# incubatorShield.net
KiCad netlist of a schematic drawn in EAGLE
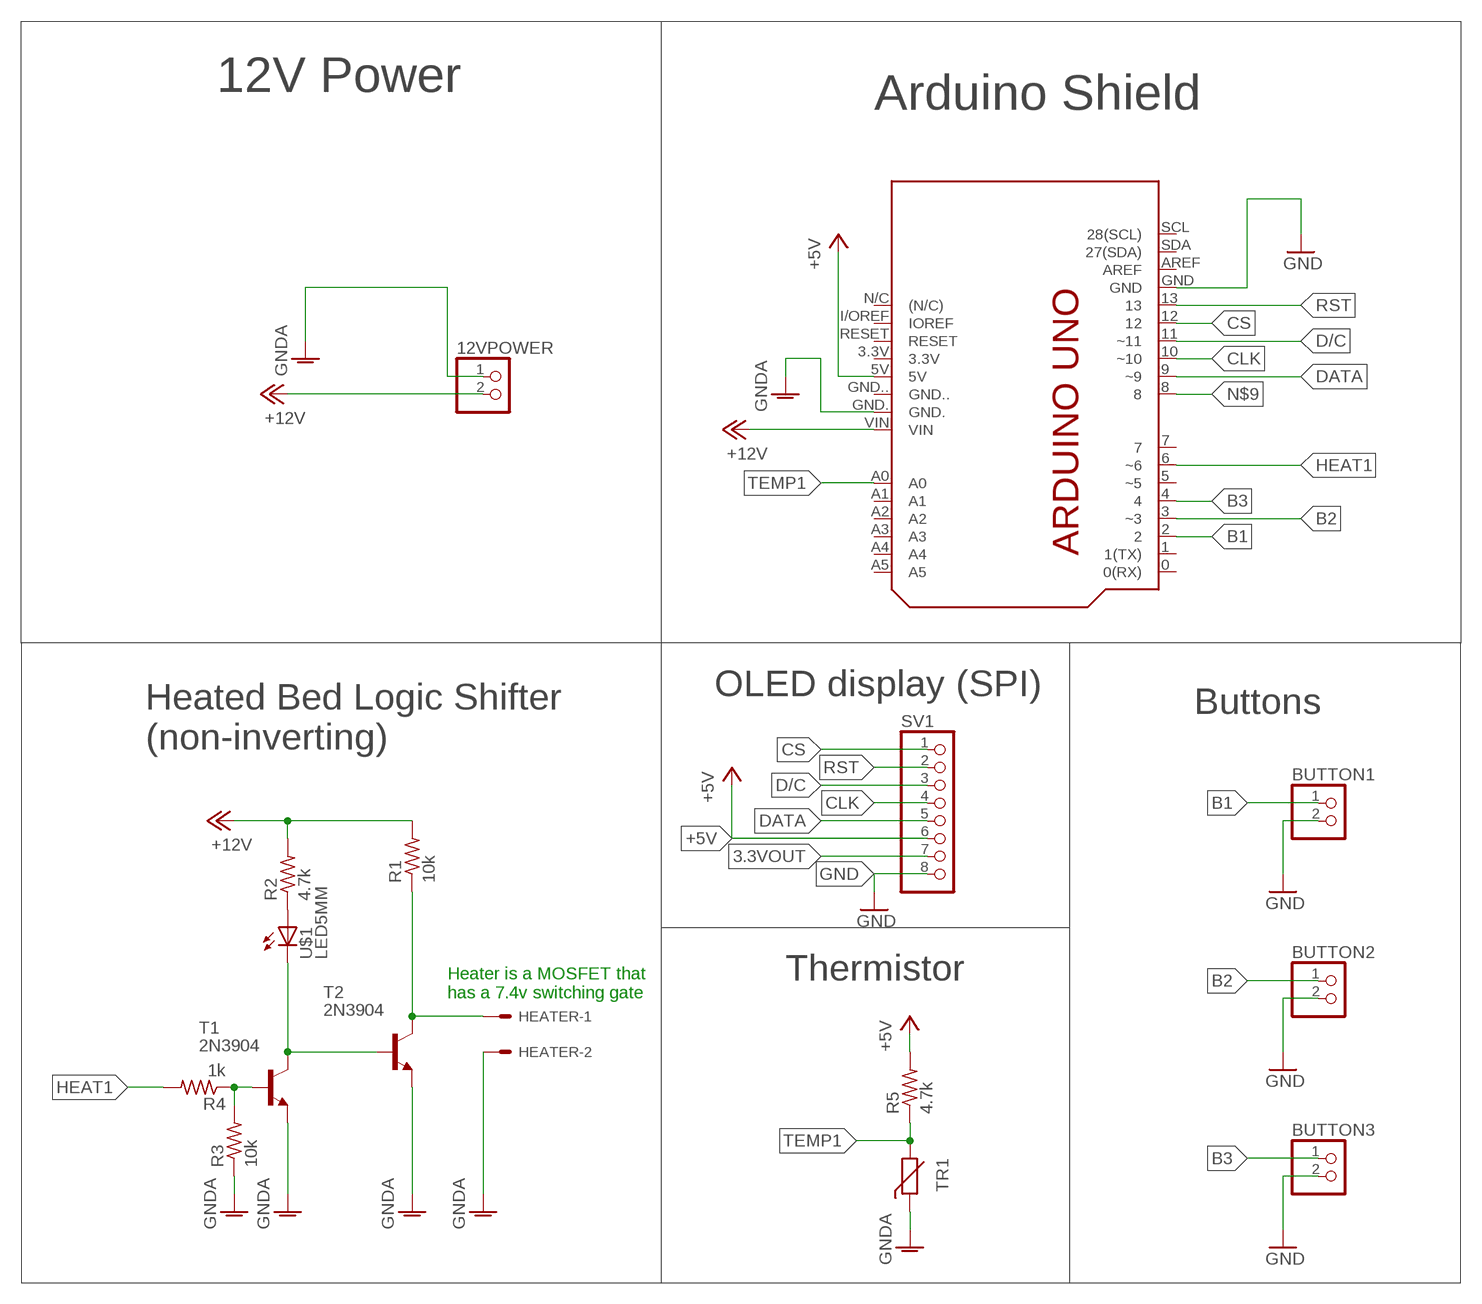
[diagram p0: schematic, sheet 1]

(export (version "E")
  (design (tool "Eeschema 10.0.6"))
  (components
    (comp (ref "12VPOWER")
      (value "PINHD-1X2")
      (footprint "eagle-import:1X02")
      (libsource (lib "eagle-import") (part "PINHD-1X2"))
    )
    (comp (ref "BUTTON1")
      (value "PINHD-1X2")
      (footprint "eagle-import:1X02")
      (libsource (lib "eagle-import") (part "PINHD-1X2"))
    )
    (comp (ref "BUTTON2")
      (value "PINHD-1X2")
      (footprint "eagle-import:1X02")
      (libsource (lib "eagle-import") (part "PINHD-1X2"))
    )
    (comp (ref "BUTTON3")
      (value "PINHD-1X2")
      (footprint "eagle-import:1X02")
      (libsource (lib "eagle-import") (part "PINHD-1X2"))
    )
    (comp (ref "HEATER")
      (value "KK-156-2")
      (footprint "eagle-import:KK-156-2")
      (fields (field (name "MF") "MOLEX"))
      (libsource (lib "eagle-import") (part "KK-156-2"))
    )
    (comp (ref "R1")
      (value "10k")
      (footprint "eagle-import:0309_12")
      (libsource (lib "eagle-import") (part "R-US_0309/12"))
    )
    (comp (ref "R2")
      (value "4.7k")
      (footprint "eagle-import:0309_12")
      (libsource (lib "eagle-import") (part "R-US_0309/12"))
    )
    (comp (ref "R3")
      (value "10k")
      (footprint "eagle-import:0309_12")
      (libsource (lib "eagle-import") (part "R-US_0309/12"))
    )
    (comp (ref "R4")
      (value "1k")
      (footprint "eagle-import:0309_12")
      (libsource (lib "eagle-import") (part "R-US_0309/12"))
    )
    (comp (ref "R5")
      (value "4.7k")
      (footprint "eagle-import:0309_12")
      (libsource (lib "eagle-import") (part "R-US_0309/12"))
    )
    (comp (ref "SV1")
      (value "PINHD-1X8")
      (footprint "eagle-import:1X08")
      (libsource (lib "eagle-import") (part "PINHD-1X8"))
    )
    (comp (ref "T1")
      (value "2N3904")
      (footprint "eagle-import:TO92")
      (libsource (lib "eagle-import") (part "2N3904"))
    )
    (comp (ref "T2")
      (value "2N3904")
      (footprint "eagle-import:TO92")
      (libsource (lib "eagle-import") (part "2N3904"))
    )
    (comp (ref "TR1")
      (value "THERMISTOR_R-2,5")
      (footprint "eagle-import:RS-2,5")
      (libsource (lib "eagle-import") (part "THERMISTOR_R-2,5"))
    )
    (comp (ref "U$1")
      (value "LED5MM")
      (footprint "eagle-import:5MM")
      (libsource (lib "eagle-import") (part "LED5MM"))
    )
    (comp (ref "U$2")
      (value "ARDUINO_UNO_UNBOUND")
      (footprint "eagle-import:ARDUINO_UNO_UNBOUND")
      (libsource (lib "eagle-import") (part "ARDUINO_UNO_UNBOUND"))
    )
  )
  (nets
    (net (code "1") (name "+5V") (class "Default")
      (node (ref "R5") (pin "2") (pinfunction "2_2") (pintype "passive"))
      (node (ref "SV1") (pin "6") (pinfunction "6_6") (pintype "passive"))
      (node (ref "U$2") (pin "5V") (pinfunction "5V_5V") (pintype "bidirectional"))
    )
    (net (code "2") (name "+12V") (class "Default")
      (node (ref "12VPOWER") (pin "2") (pinfunction "2_2") (pintype "passive"))
      (node (ref "R1") (pin "2") (pinfunction "2_2") (pintype "passive"))
      (node (ref "R2") (pin "2") (pinfunction "2_2") (pintype "passive"))
      (node (ref "U$2") (pin "VIN") (pinfunction "VIN_VIN") (pintype "bidirectional"))
    )
    (net (code "3") (name "3.3VOUT") (class "Default")
      (node (ref "SV1") (pin "7") (pinfunction "7_7") (pintype "passive"))
    )
    (net (code "4") (name "B1") (class "Default")
      (node (ref "BUTTON1") (pin "1") (pinfunction "1_1") (pintype "passive"))
      (node (ref "U$2") (pin "2") (pinfunction "2_2") (pintype "bidirectional"))
    )
    (net (code "5") (name "B2") (class "Default")
      (node (ref "BUTTON2") (pin "1") (pinfunction "1_1") (pintype "passive"))
      (node (ref "U$2") (pin "3") (pinfunction "~{3}_3") (pintype "bidirectional"))
    )
    (net (code "6") (name "B3") (class "Default")
      (node (ref "BUTTON3") (pin "1") (pinfunction "1_1") (pintype "passive"))
      (node (ref "U$2") (pin "4") (pinfunction "4_4") (pintype "bidirectional"))
    )
    (net (code "7") (name "CLK") (class "Default")
      (node (ref "SV1") (pin "4") (pinfunction "4_4") (pintype "passive"))
      (node (ref "U$2") (pin "10") (pinfunction "~{10}_10") (pintype "bidirectional"))
    )
    (net (code "8") (name "CS") (class "Default")
      (node (ref "SV1") (pin "1") (pinfunction "1_1") (pintype "passive"))
      (node (ref "U$2") (pin "12") (pinfunction "12_12") (pintype "bidirectional"))
    )
    (net (code "9") (name "DATA") (class "Default")
      (node (ref "SV1") (pin "5") (pinfunction "5_5") (pintype "passive"))
      (node (ref "U$2") (pin "9") (pinfunction "~{9}_9") (pintype "bidirectional"))
    )
    (net (code "10") (name "D{slash}C") (class "Default")
      (node (ref "SV1") (pin "3") (pinfunction "3_3") (pintype "passive"))
      (node (ref "U$2") (pin "11") (pinfunction "~{11}_11") (pintype "bidirectional"))
    )
    (net (code "11") (name "GND") (class "Default")
      (node (ref "BUTTON1") (pin "2") (pinfunction "2_2") (pintype "passive"))
      (node (ref "BUTTON2") (pin "2") (pinfunction "2_2") (pintype "passive"))
      (node (ref "BUTTON3") (pin "2") (pinfunction "2_2") (pintype "passive"))
      (node (ref "SV1") (pin "8") (pinfunction "8_8") (pintype "passive"))
      (node (ref "U$2") (pin "GND") (pinfunction "GND_GND") (pintype "bidirectional"))
    )
    (net (code "12") (name "GNDA") (class "Default")
      (node (ref "12VPOWER") (pin "1") (pinfunction "1_1") (pintype "passive"))
      (node (ref "HEATER") (pin "2") (pinfunction "S_2") (pintype "passive"))
      (node (ref "R3") (pin "1") (pinfunction "1_1") (pintype "passive"))
      (node (ref "T1") (pin "3") (pinfunction "E_3") (pintype "passive"))
      (node (ref "T2") (pin "3") (pinfunction "E_3") (pintype "passive"))
      (node (ref "TR1") (pin "1") (pinfunction "1_1") (pintype "passive"))
      (node (ref "U$2") (pin "GND.") (pinfunction "GND._GND.") (pintype "bidirectional"))
    )
    (net (code "13") (name "HEAT1") (class "Default")
      (node (ref "R4") (pin "2") (pinfunction "2_2") (pintype "passive"))
      (node (ref "U$2") (pin "6") (pinfunction "~{6}_6") (pintype "bidirectional"))
    )
    (net (code "14") (name "N$9") (class "Default")
      (node (ref "U$2") (pin "8") (pinfunction "8_8") (pintype "bidirectional"))
    )
    (net (code "15") (name "Net-(HEATERA-S)") (class "Default")
      (node (ref "HEATER") (pin "1") (pinfunction "S_1") (pintype "passive"))
      (node (ref "R1") (pin "1") (pinfunction "1_1") (pintype "passive"))
      (node (ref "T2") (pin "1") (pinfunction "C_1") (pintype "passive"))
    )
    (net (code "16") (name "Net-(T1-B)") (class "Default")
      (node (ref "R3") (pin "2") (pinfunction "2_2") (pintype "passive"))
      (node (ref "R4") (pin "1") (pinfunction "1_1") (pintype "passive"))
      (node (ref "T1") (pin "2") (pinfunction "B_2") (pintype "passive"))
    )
    (net (code "17") (name "Net-(T1-C)") (class "Default")
      (node (ref "T1") (pin "1") (pinfunction "C_1") (pintype "passive"))
      (node (ref "T2") (pin "2") (pinfunction "B_2") (pintype "passive"))
      (node (ref "U$1") (pin "OUT") (pinfunction "C_OUT") (pintype "passive"))
    )
    (net (code "18") (name "Net-(U$1-A)") (class "Default")
      (node (ref "R2") (pin "1") (pinfunction "1_1") (pintype "passive"))
      (node (ref "U$1") (pin "IN") (pinfunction "A_IN") (pintype "passive"))
    )
    (net (code "19") (name "RST") (class "Default")
      (node (ref "SV1") (pin "2") (pinfunction "2_2") (pintype "passive"))
      (node (ref "U$2") (pin "13") (pinfunction "13_13") (pintype "bidirectional"))
    )
    (net (code "20") (name "TEMP1") (class "Default")
      (node (ref "R5") (pin "1") (pinfunction "1_1") (pintype "passive"))
      (node (ref "TR1") (pin "2") (pinfunction "2_2") (pintype "passive"))
      (node (ref "U$2") (pin "A0") (pinfunction "A0_A0") (pintype "bidirectional"))
    )
    (net (code "21") (name "unconnected-(U$2-(N{slash}C)-PadN{slash}C)") (class "Default")
      (node (ref "U$2") (pin "N/C") (pinfunction "(N/C)_N/C") (pintype "bidirectional"))
    )
    (net (code "22") (name "unconnected-(U$2-0(RX)-Pad0)") (class "Default")
      (node (ref "U$2") (pin "0") (pinfunction "0(RX)_0") (pintype "bidirectional"))
    )
    (net (code "23") (name "unconnected-(U$2-1(TX)-Pad1)") (class "Default")
      (node (ref "U$2") (pin "1") (pinfunction "1(TX)_1") (pintype "bidirectional"))
    )
    (net (code "24") (name "unconnected-(U$2-27(SDA)-PadSDA)") (class "Default")
      (node (ref "U$2") (pin "SDA") (pinfunction "27(SDA)_SDA") (pintype "bidirectional"))
    )
    (net (code "25") (name "unconnected-(U$2-28(SCL)-PadSCL)") (class "Default")
      (node (ref "U$2") (pin "SCL") (pinfunction "28(SCL)_SCL") (pintype "bidirectional"))
    )
    (net (code "26") (name "unconnected-(U$2-IOREF-PadI{slash}OREF)") (class "Default")
      (node (ref "U$2") (pin "I/OREF") (pinfunction "IOREF_I/OREF") (pintype "bidirectional"))
    )
    (net (code "27") (name "unconnected-(U$2-Pad3.3V)") (class "Default")
      (node (ref "U$2") (pin "3.3V") (pinfunction "3.3V_3.3V") (pintype "bidirectional"))
    )
    (net (code "28") (name "unconnected-(U$2-Pad7)") (class "Default")
      (node (ref "U$2") (pin "7") (pinfunction "7_7") (pintype "bidirectional"))
    )
    (net (code "29") (name "unconnected-(U$2-PadA1)") (class "Default")
      (node (ref "U$2") (pin "A1") (pinfunction "A1_A1") (pintype "bidirectional"))
    )
    (net (code "30") (name "unconnected-(U$2-PadA2)") (class "Default")
      (node (ref "U$2") (pin "A2") (pinfunction "A2_A2") (pintype "bidirectional"))
    )
    (net (code "31") (name "unconnected-(U$2-PadA3)") (class "Default")
      (node (ref "U$2") (pin "A3") (pinfunction "A3_A3") (pintype "bidirectional"))
    )
    (net (code "32") (name "unconnected-(U$2-PadA4)") (class "Default")
      (node (ref "U$2") (pin "A4") (pinfunction "A4_A4") (pintype "bidirectional"))
    )
    (net (code "33") (name "unconnected-(U$2-PadA5)") (class "Default")
      (node (ref "U$2") (pin "A5") (pinfunction "A5_A5") (pintype "bidirectional"))
    )
    (net (code "34") (name "unconnected-(U$2-PadAREF)") (class "Default")
      (node (ref "U$2") (pin "AREF") (pinfunction "AREF_AREF") (pintype "bidirectional"))
    )
    (net (code "35") (name "unconnected-(U$2-PadGND..)") (class "Default")
      (node (ref "U$2") (pin "GND..") (pinfunction "GND.._GND..") (pintype "bidirectional"))
    )
    (net (code "36") (name "unconnected-(U$2-PadRESET)") (class "Default")
      (node (ref "U$2") (pin "RESET") (pinfunction "RESET_RESET") (pintype "bidirectional"))
    )
    (net (code "37") (name "unconnected-(U$2-~{5}-Pad5)") (class "Default")
      (node (ref "U$2") (pin "5") (pinfunction "~{5}_5") (pintype "bidirectional"))
    )
  )
)
